# SPI_Breakout.net
KiCad netlist of a schematic drawn in Altium Designer
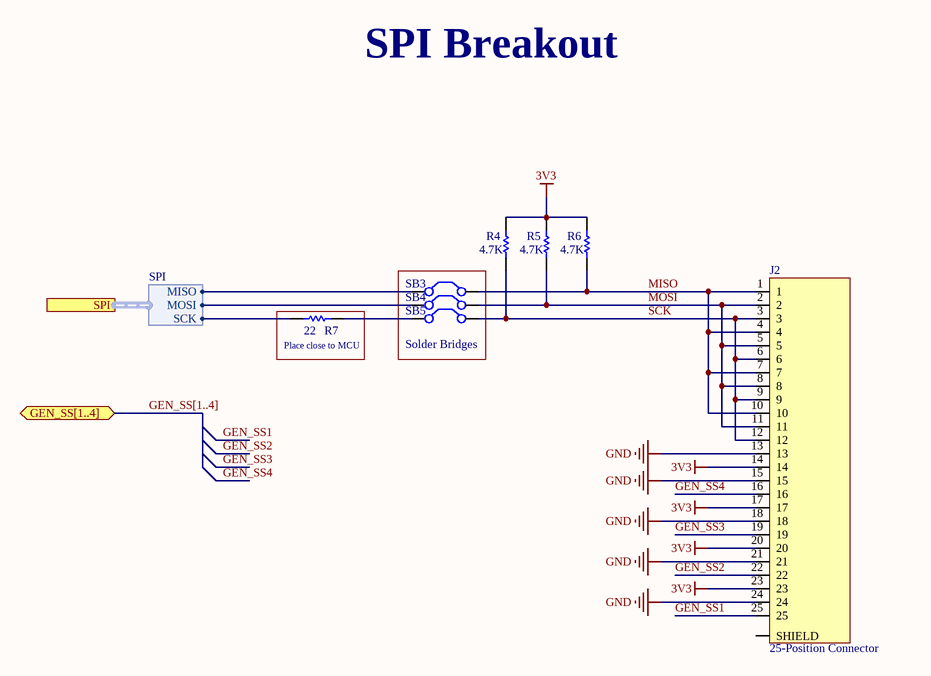
[diagram p0: SPI_Breakout.SchDoc]

(export (version "E")
  (design (tool "Eeschema 10.0.6"))
  (components
    (comp (ref "J2")
      (value "25-Position Connector")
      (footprint "25-POS D-SUB")
      (fields
        (field (name "DIGIKEY PART NUMBER") "NOR1066-ND")
        (field (name "MANUFACTURER PART NUMBER") "772-E25-213R051")
      )
      (libsource (lib "LaunchyRIOComponents") (part "25-Position Connector"))
    )
    (comp (ref "R4")
      (value "4.7K")
      (footprint "0402")
      (description "Resistor")
      (fields (field (name "Comment") "Res1"))
      (libsource (lib "Miscellaneous Devices") (part "Res1"))
    )
    (comp (ref "R5")
      (value "4.7K")
      (footprint "0402")
      (description "Resistor")
      (fields (field (name "Comment") "Res1"))
      (libsource (lib "Miscellaneous Devices") (part "Res1"))
    )
    (comp (ref "R6")
      (value "4.7K")
      (footprint "0402")
      (description "Resistor")
      (fields (field (name "Comment") "Res1"))
      (libsource (lib "Miscellaneous Devices") (part "Res1"))
    )
    (comp (ref "R7")
      (value "22")
      (footprint "0402")
      (description "Resistor")
      (fields (field (name "Comment") "Res1"))
      (libsource (lib "Miscellaneous Devices") (part "Res1"))
    )
    (comp (ref "SB3")
      (value "Solder Bridge")
      (footprint "SB-2pos")
      (description "Jumper Wire")
      (libsource (lib "Miscellaneous Devices") (part "Jumper"))
    )
    (comp (ref "SB4")
      (value "Solder Bridge")
      (footprint "SB-2pos")
      (description "Jumper Wire")
      (libsource (lib "Miscellaneous Devices") (part "Jumper"))
    )
    (comp (ref "SB5")
      (value "Solder Bridge")
      (footprint "SB-2pos")
      (description "Jumper Wire")
      (libsource (lib "Miscellaneous Devices") (part "Jumper"))
    )
  )
  (nets
    (net (code "2") (name "/GEN_SS1") (class "Default")
      (node (ref "J2") (pin "25") (pinfunction "25_25") (pintype "bidirectional"))
    )
    (net (code "3") (name "/GEN_SS2") (class "Default")
      (node (ref "J2") (pin "22") (pinfunction "22_22") (pintype "bidirectional"))
    )
    (net (code "4") (name "/GEN_SS3") (class "Default")
      (node (ref "J2") (pin "19") (pinfunction "19_19") (pintype "bidirectional"))
    )
    (net (code "5") (name "/GEN_SS4") (class "Default")
      (node (ref "J2") (pin "16") (pinfunction "16_16") (pintype "bidirectional"))
    )
    (net (code "7") (name "/MISO") (class "Default")
      (node (ref "J2") (pin "1") (pinfunction "1_1") (pintype "bidirectional"))
      (node (ref "J2") (pin "10") (pinfunction "10_10") (pintype "bidirectional"))
      (node (ref "J2") (pin "4") (pinfunction "4_4") (pintype "bidirectional"))
      (node (ref "J2") (pin "7") (pinfunction "7_7") (pintype "bidirectional"))
      (node (ref "R6") (pin "2") (pinfunction "2_2") (pintype "passive"))
      (node (ref "SB3") (pin "2") (pinfunction "C2_2") (pintype "passive"))
    )
    (net (code "8") (name "/MOSI") (class "Default")
      (node (ref "J2") (pin "11") (pinfunction "11_11") (pintype "bidirectional"))
      (node (ref "J2") (pin "2") (pinfunction "2_2") (pintype "bidirectional"))
      (node (ref "J2") (pin "5") (pinfunction "5_5") (pintype "bidirectional"))
      (node (ref "J2") (pin "8") (pinfunction "8_8") (pintype "bidirectional"))
      (node (ref "R5") (pin "1") (pinfunction "1_1") (pintype "passive"))
      (node (ref "SB4") (pin "2") (pinfunction "C2_2") (pintype "passive"))
    )
    (net (code "9") (name "/SCK") (class "Default")
      (node (ref "J2") (pin "12") (pinfunction "12_12") (pintype "bidirectional"))
      (node (ref "J2") (pin "3") (pinfunction "3_3") (pintype "bidirectional"))
      (node (ref "J2") (pin "6") (pinfunction "6_6") (pintype "bidirectional"))
      (node (ref "J2") (pin "9") (pinfunction "9_9") (pintype "bidirectional"))
      (node (ref "R4") (pin "2") (pinfunction "2_2") (pintype "passive"))
      (node (ref "SB5") (pin "2") (pinfunction "C2_2") (pintype "passive"))
    )
    (net (code "11") (name "3V3") (class "Default")
      (node (ref "J2") (pin "14") (pinfunction "14_14") (pintype "bidirectional"))
      (node (ref "J2") (pin "17") (pinfunction "17_17") (pintype "bidirectional"))
      (node (ref "J2") (pin "20") (pinfunction "20_20") (pintype "bidirectional"))
      (node (ref "J2") (pin "23") (pinfunction "23_23") (pintype "bidirectional"))
      (node (ref "R4") (pin "1") (pinfunction "1_1") (pintype "passive"))
      (node (ref "R5") (pin "2") (pinfunction "2_2") (pintype "passive"))
      (node (ref "R6") (pin "1") (pinfunction "1_1") (pintype "passive"))
    )
    (net (code "12") (name "GND") (class "Default")
      (node (ref "J2") (pin "13") (pinfunction "13_13") (pintype "bidirectional"))
      (node (ref "J2") (pin "15") (pinfunction "15_15") (pintype "bidirectional"))
      (node (ref "J2") (pin "18") (pinfunction "18_18") (pintype "bidirectional"))
      (node (ref "J2") (pin "21") (pinfunction "21_21") (pintype "bidirectional"))
      (node (ref "J2") (pin "24") (pinfunction "24_24") (pintype "bidirectional"))
    )
    (net (code "13") (name "Net-(SB5-C1)") (class "Default")
      (node (ref "R7") (pin "2") (pinfunction "2_2") (pintype "passive"))
      (node (ref "SB5") (pin "1") (pinfunction "C1_1") (pintype "passive"))
    )
    (net (code "14") (name "unconnected-(J2-PadSHIELD)") (class "Default")
      (node (ref "J2") (pin "SHIELD") (pinfunction "SHIELD_SHIELD") (pintype "passive"))
    )
    (net (code "15") (name "unconnected-(R7-Pad1)") (class "Default")
      (node (ref "R7") (pin "1") (pinfunction "1_1") (pintype "passive"))
    )
    (net (code "16") (name "unconnected-(SB3-C1-Pad1)") (class "Default")
      (node (ref "SB3") (pin "1") (pinfunction "C1_1") (pintype "passive"))
    )
    (net (code "17") (name "unconnected-(SB4-C1-Pad1)") (class "Default")
      (node (ref "SB4") (pin "1") (pinfunction "C1_1") (pintype "passive"))
    )
  )
)
